# md.net
KiCad netlist of a schematic drawn in EAGLE
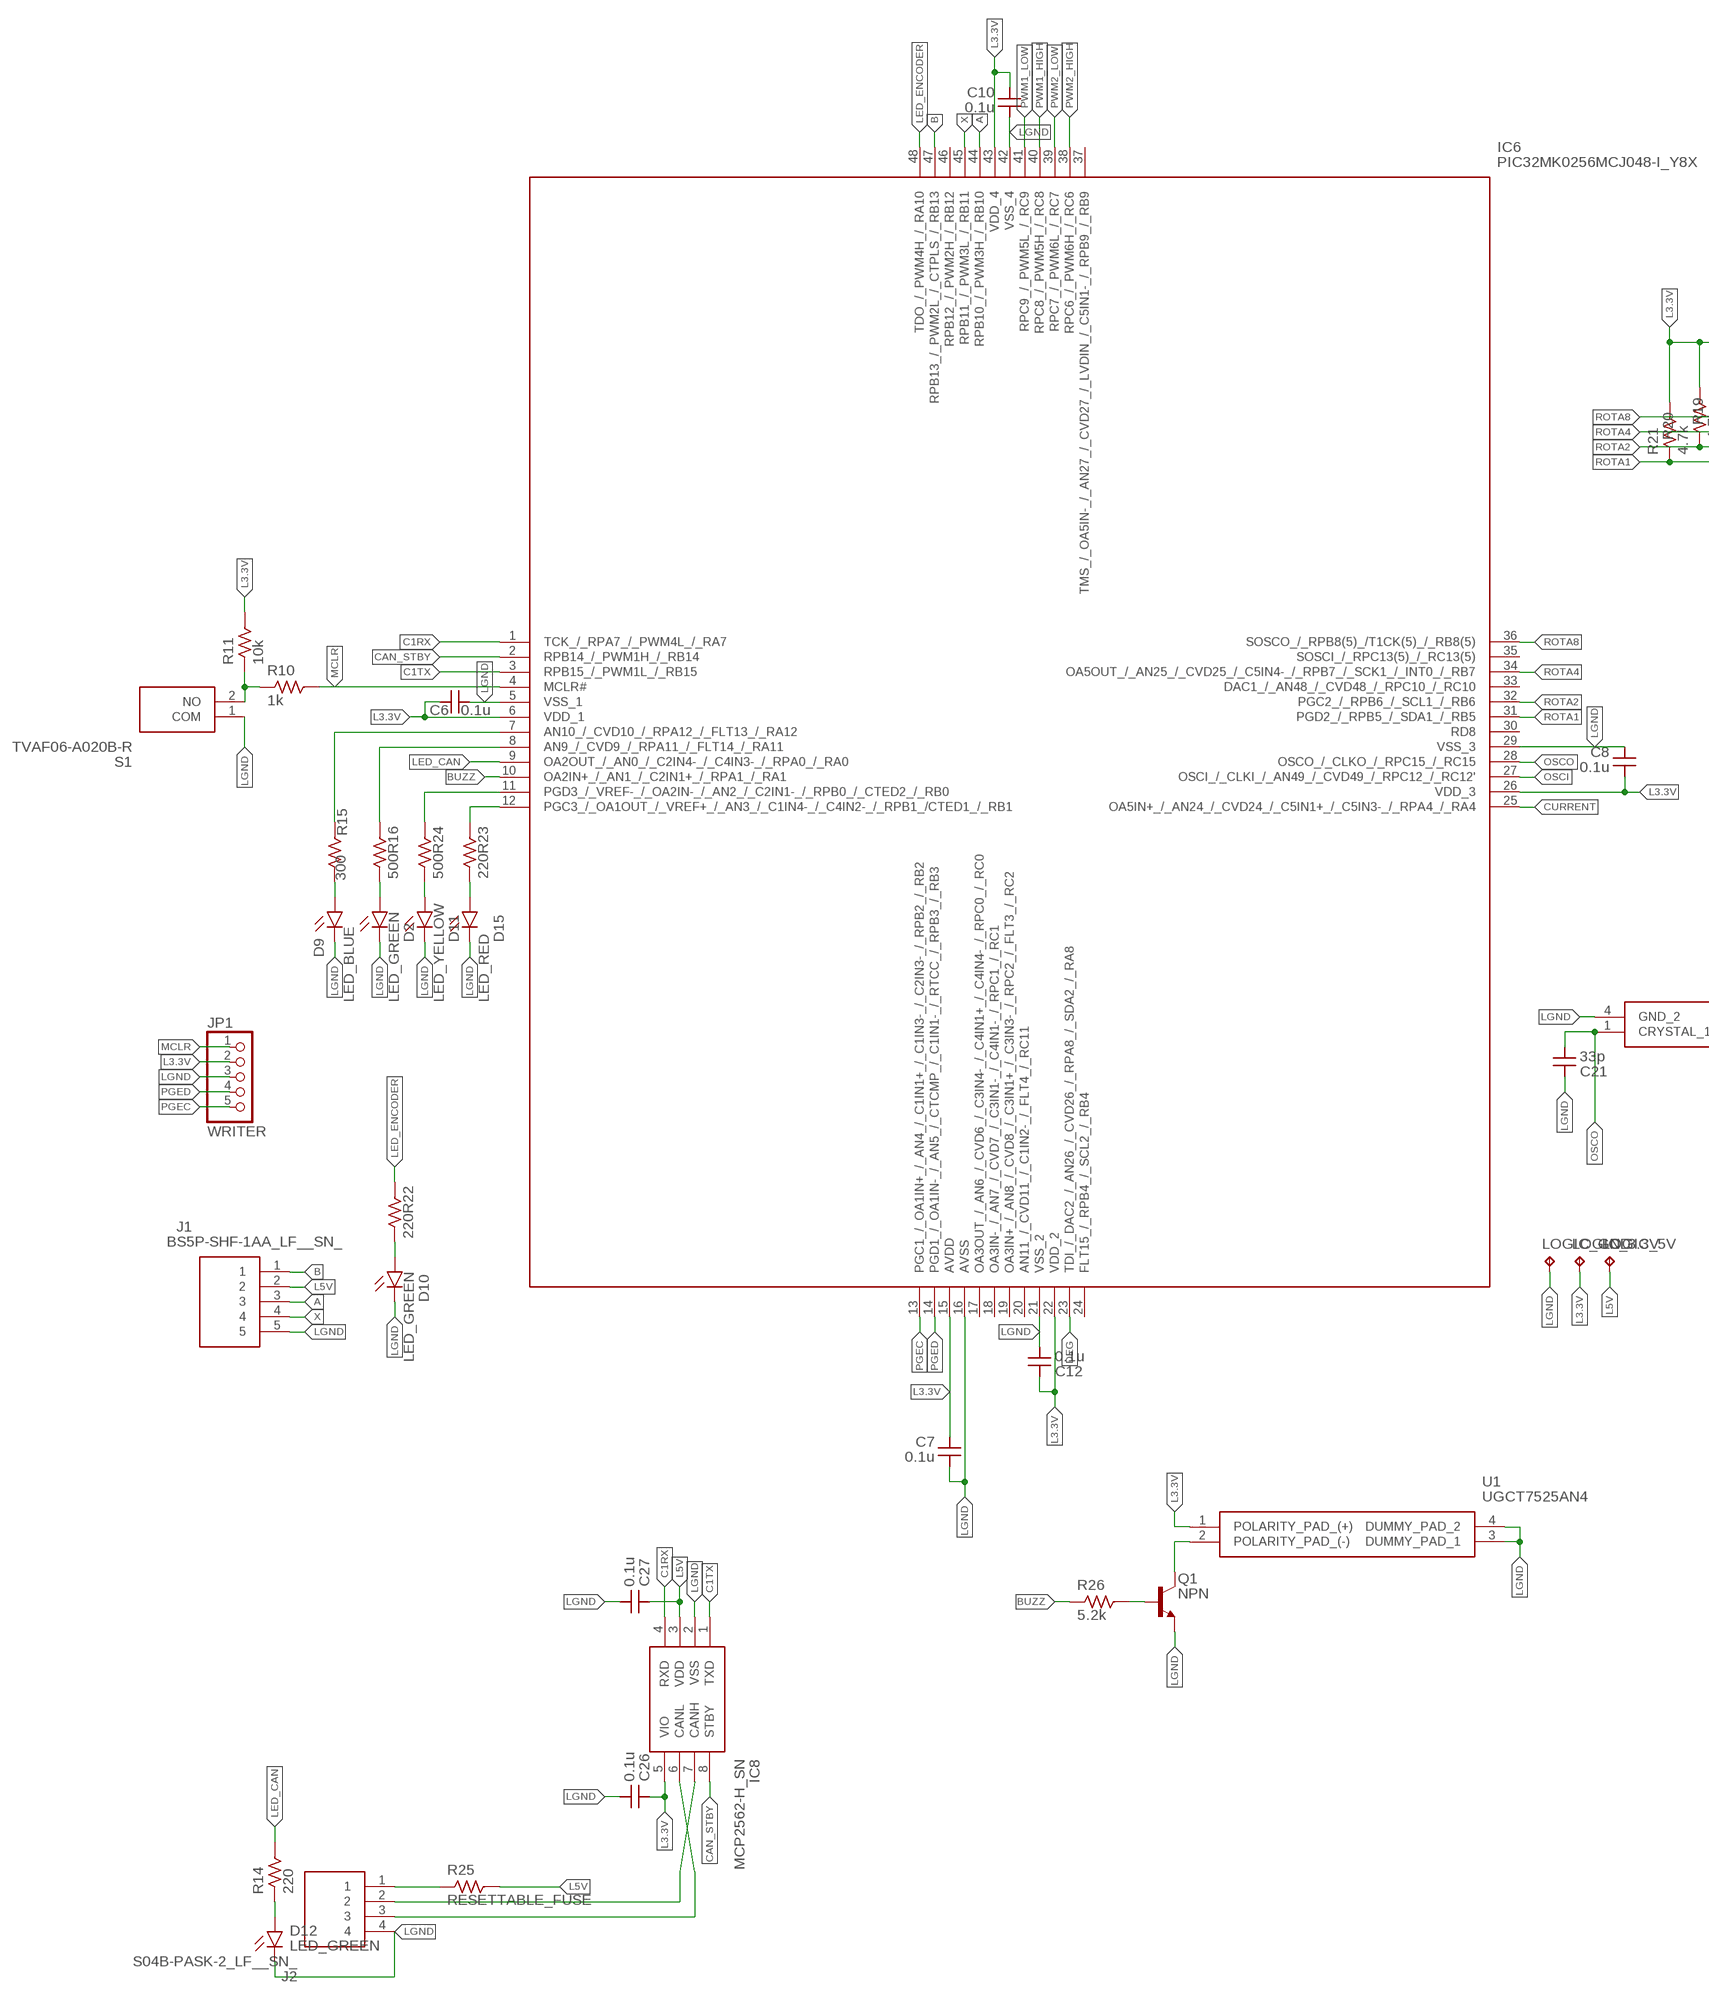
[diagram p0: schematic, sheet 1, part 1 of 2]
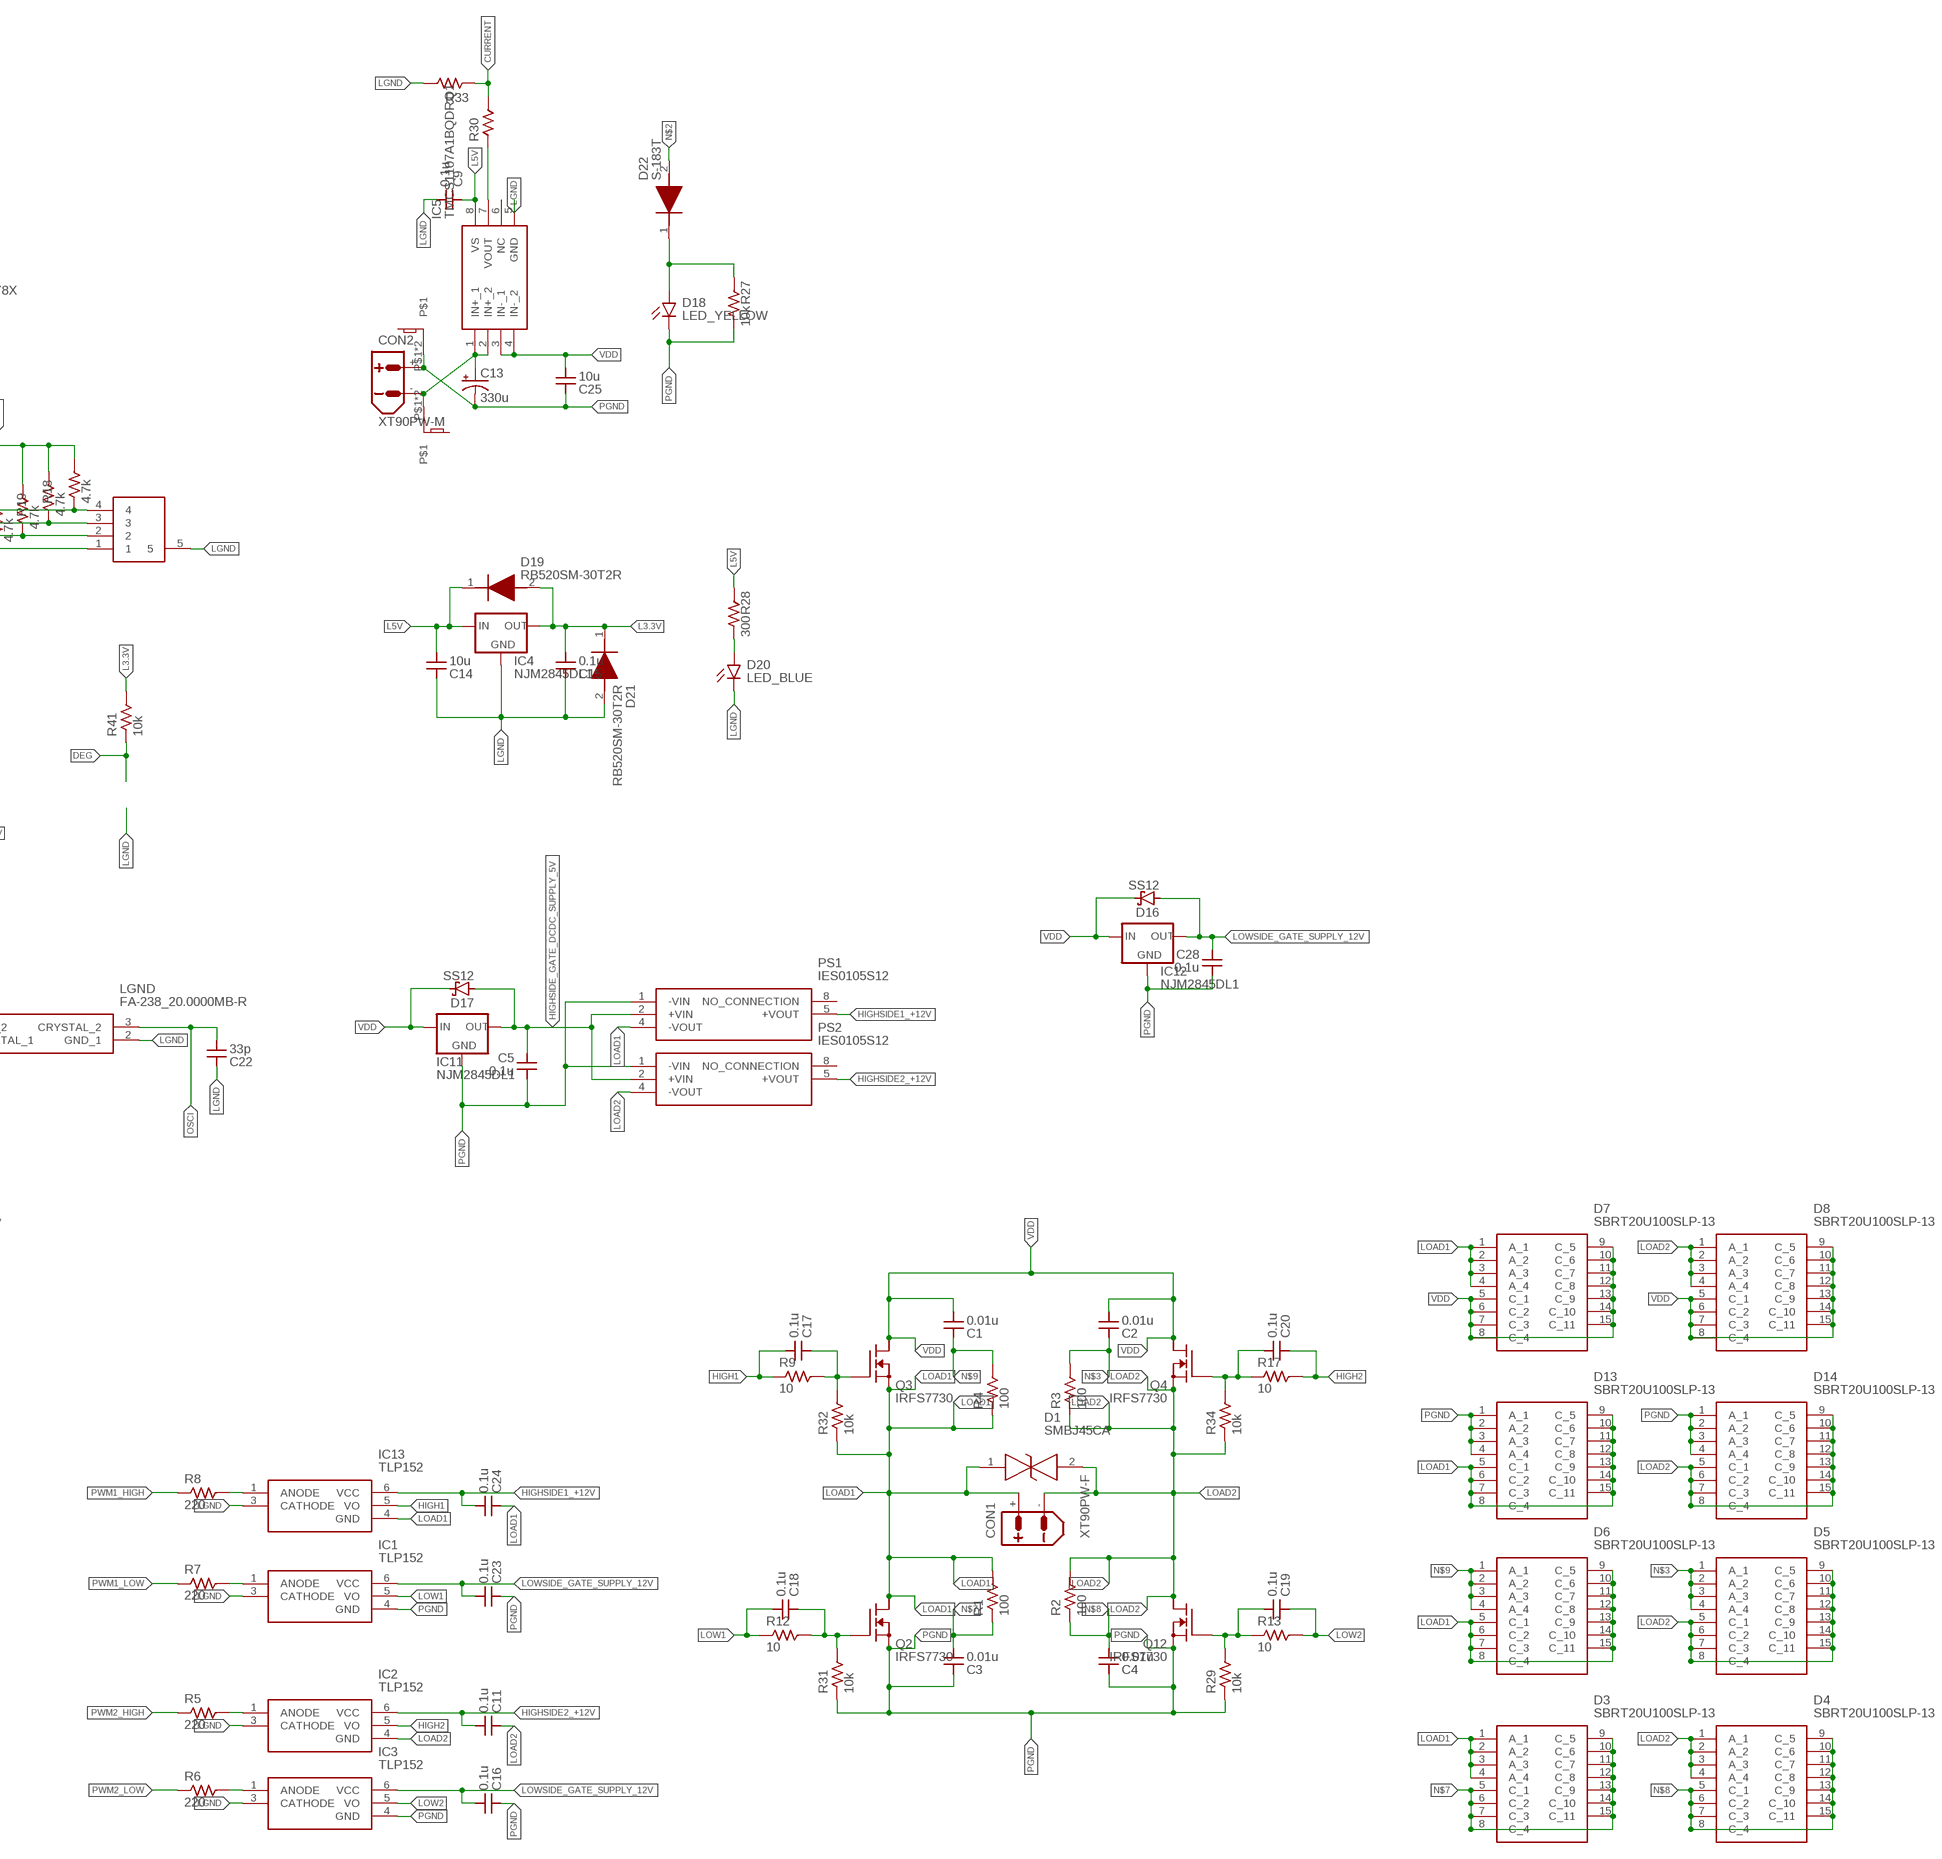
[diagram p1: schematic, sheet 1, part 2 of 2]

(export (version "E")
  (design (tool "Eeschema 10.0.6"))
  (components
    (comp (ref "C1")
      (value "0.01u")
      (footprint "eagle-import:C3216")
      (libsource (lib "eagle-import") (part "CC3216"))
    )
    (comp (ref "C2")
      (value "0.01u")
      (footprint "eagle-import:C3216")
      (libsource (lib "eagle-import") (part "CC3216"))
    )
    (comp (ref "C3")
      (value "0.01u")
      (footprint "eagle-import:C3216")
      (libsource (lib "eagle-import") (part "CC3216"))
    )
    (comp (ref "C4")
      (value "0.01u")
      (footprint "eagle-import:C3216")
      (libsource (lib "eagle-import") (part "CC3216"))
    )
    (comp (ref "C5")
      (value "0.1u")
      (footprint "eagle-import:C1608")
      (libsource (lib "eagle-import") (part "CC1068"))
    )
    (comp (ref "C6")
      (value "0.1u")
      (footprint "eagle-import:C1608")
      (libsource (lib "eagle-import") (part "CC1068"))
    )
    (comp (ref "C7")
      (value "0.1u")
      (footprint "eagle-import:C1608")
      (libsource (lib "eagle-import") (part "CC1068"))
    )
    (comp (ref "C8")
      (value "0.1u")
      (footprint "eagle-import:C1608")
      (libsource (lib "eagle-import") (part "CC1068"))
    )
    (comp (ref "C9")
      (value "0.1u")
      (footprint "eagle-import:C1608")
      (libsource (lib "eagle-import") (part "CC1068"))
    )
    (comp (ref "C10")
      (value "0.1u")
      (footprint "eagle-import:C1608")
      (libsource (lib "eagle-import") (part "CC1068"))
    )
    (comp (ref "C11")
      (value "0.1u")
      (footprint "eagle-import:C1608")
      (libsource (lib "eagle-import") (part "CC1068"))
    )
    (comp (ref "C12")
      (value "0.1u")
      (footprint "eagle-import:C1608")
      (libsource (lib "eagle-import") (part "CC1068"))
    )
    (comp (ref "C13")
      (value "330u")
      (footprint "eagle-import:CAPAE830X1050N")
      (libsource (lib "eagle-import") (part "C-POL-USECAP-8.5MM_"))
    )
    (comp (ref "C14")
      (value "10u")
      (footprint "eagle-import:C1608")
      (libsource (lib "eagle-import") (part "CC1068"))
    )
    (comp (ref "C15")
      (value "0.1u")
      (footprint "eagle-import:C1608")
      (libsource (lib "eagle-import") (part "CC1068"))
    )
    (comp (ref "C16")
      (value "0.1u")
      (footprint "eagle-import:C1608")
      (libsource (lib "eagle-import") (part "CC1068"))
    )
    (comp (ref "C17")
      (value "0.1u")
      (footprint "eagle-import:C1608")
      (libsource (lib "eagle-import") (part "CC1068"))
    )
    (comp (ref "C18")
      (value "0.1u")
      (footprint "eagle-import:C1608")
      (libsource (lib "eagle-import") (part "CC1068"))
    )
    (comp (ref "C19")
      (value "0.1u")
      (footprint "eagle-import:C1608")
      (libsource (lib "eagle-import") (part "CC1068"))
    )
    (comp (ref "C20")
      (value "0.1u")
      (footprint "eagle-import:C1608")
      (libsource (lib "eagle-import") (part "CC1068"))
    )
    (comp (ref "C21")
      (value "33p")
      (footprint "eagle-import:C1608")
      (libsource (lib "eagle-import") (part "CC1068"))
    )
    (comp (ref "C22")
      (value "33p")
      (footprint "eagle-import:C1608")
      (libsource (lib "eagle-import") (part "CC1068"))
    )
    (comp (ref "C23")
      (value "0.1u")
      (footprint "eagle-import:C1608")
      (libsource (lib "eagle-import") (part "CC1068"))
    )
    (comp (ref "C24")
      (value "0.1u")
      (footprint "eagle-import:C1608")
      (libsource (lib "eagle-import") (part "CC1068"))
    )
    (comp (ref "C25")
      (value "10u")
      (footprint "eagle-import:C3216")
      (libsource (lib "eagle-import") (part "CC3216"))
    )
    (comp (ref "C26")
      (value "0.1u")
      (footprint "eagle-import:C1608")
      (libsource (lib "eagle-import") (part "CC1068"))
    )
    (comp (ref "C27")
      (value "0.1u")
      (footprint "eagle-import:C1608")
      (libsource (lib "eagle-import") (part "CC1068"))
    )
    (comp (ref "C28")
      (value "0.1u")
      (footprint "eagle-import:C1608")
      (libsource (lib "eagle-import") (part "CC1068"))
    )
    (comp (ref "CON1")
      (value "XT90PW-F")
      (footprint "eagle-import:XT90PW-F")
      (libsource (lib "eagle-import") (part "XT90PW-F"))
    )
    (comp (ref "CON2")
      (value "XT90PW-M")
      (footprint "eagle-import:XT90PW-M")
      (libsource (lib "eagle-import") (part "XT90PW-M"))
    )
    (comp (ref "D1")
      (value "SMBJ45CA")
      (footprint "eagle-import:DIOM5336X265N")
      (fields (field (name "MOUSER_PART_NUMBER") "576-SMBJ45CA"))
      (libsource (lib "eagle-import") (part "SMBJ45CA"))
    )
    (comp (ref "D2")
      (value "LED_GREEN")
      (footprint "eagle-import:LEDC1608X55N_FLAT-G")
      (libsource (lib "eagle-import") (part "CHIP-FLAT-G_0603-0.55MM"))
    )
    (comp (ref "D3")
      (value "SBRT20U100SLP-13")
      (footprint "eagle-import:SBRT20U100SLP13")
      (fields (field (name "MOUSER_PART_NUMBER") "621-SBRT20U100SLP-13"))
      (libsource (lib "eagle-import") (part "SBRT20U100SLP-13"))
    )
    (comp (ref "D4")
      (value "SBRT20U100SLP-13")
      (footprint "eagle-import:SBRT20U100SLP13")
      (fields (field (name "MOUSER_PART_NUMBER") "621-SBRT20U100SLP-13"))
      (libsource (lib "eagle-import") (part "SBRT20U100SLP-13"))
    )
    (comp (ref "D5")
      (value "SBRT20U100SLP-13")
      (footprint "eagle-import:SBRT20U100SLP13")
      (fields (field (name "MOUSER_PART_NUMBER") "621-SBRT20U100SLP-13"))
      (libsource (lib "eagle-import") (part "SBRT20U100SLP-13"))
    )
    (comp (ref "D6")
      (value "SBRT20U100SLP-13")
      (footprint "eagle-import:SBRT20U100SLP13")
      (fields (field (name "MOUSER_PART_NUMBER") "621-SBRT20U100SLP-13"))
      (libsource (lib "eagle-import") (part "SBRT20U100SLP-13"))
    )
    (comp (ref "D7")
      (value "SBRT20U100SLP-13")
      (footprint "eagle-import:SBRT20U100SLP13")
      (fields (field (name "MOUSER_PART_NUMBER") "621-SBRT20U100SLP-13"))
      (libsource (lib "eagle-import") (part "SBRT20U100SLP-13"))
    )
    (comp (ref "D8")
      (value "SBRT20U100SLP-13")
      (footprint "eagle-import:SBRT20U100SLP13")
      (fields (field (name "MOUSER_PART_NUMBER") "621-SBRT20U100SLP-13"))
      (libsource (lib "eagle-import") (part "SBRT20U100SLP-13"))
    )
    (comp (ref "D9")
      (value "LED_BLUE")
      (footprint "eagle-import:LEDC1608X55N_FLAT-B")
      (libsource (lib "eagle-import") (part "CHIP-FLAT-B_0603-0.55MM"))
    )
    (comp (ref "D10")
      (value "LED_GREEN")
      (footprint "eagle-import:LEDC1608X55N_FLAT-G")
      (libsource (lib "eagle-import") (part "CHIP-FLAT-G_0603-0.55MM"))
    )
    (comp (ref "D11")
      (value "LED_YELLOW")
      (footprint "eagle-import:LEDC1608X55N_FLAT-Y")
      (libsource (lib "eagle-import") (part "CHIP-FLAT-Y_0603-0.55MM"))
    )
    (comp (ref "D12")
      (value "LED_GREEN")
      (footprint "eagle-import:LEDC1608X55N_FLAT-G")
      (libsource (lib "eagle-import") (part "CHIP-FLAT-G_0603-0.55MM"))
    )
    (comp (ref "D13")
      (value "SBRT20U100SLP-13")
      (footprint "eagle-import:SBRT20U100SLP13")
      (fields (field (name "MOUSER_PART_NUMBER") "621-SBRT20U100SLP-13"))
      (libsource (lib "eagle-import") (part "SBRT20U100SLP-13"))
    )
    (comp (ref "D14")
      (value "SBRT20U100SLP-13")
      (footprint "eagle-import:SBRT20U100SLP13")
      (fields (field (name "MOUSER_PART_NUMBER") "621-SBRT20U100SLP-13"))
      (libsource (lib "eagle-import") (part "SBRT20U100SLP-13"))
    )
    (comp (ref "D15")
      (value "LED_RED")
      (footprint "eagle-import:LEDC1608X55N_FLAT-R")
      (libsource (lib "eagle-import") (part "CHIP-FLAT-R_0603-0.55MM"))
    )
    (comp (ref "D16")
      (value "SS12")
      (footprint "eagle-import:SMA")
      (fields
        (field (name "DIGIKEY_PART_NUMBER") "SS12FSCT-ND")
        (field (name "MANUFACTURER") "ON Semiconductor")
        (field (name "CREATED_BY") "PCBLayout.com")
      )
      (libsource (lib "eagle-import") (part "SS12"))
    )
    (comp (ref "D17")
      (value "SS12")
      (footprint "eagle-import:SMA")
      (fields
        (field (name "DIGIKEY_PART_NUMBER") "SS12FSCT-ND")
        (field (name "MANUFACTURER") "ON Semiconductor")
        (field (name "CREATED_BY") "PCBLayout.com")
      )
      (libsource (lib "eagle-import") (part "SS12"))
    )
    (comp (ref "D18")
      (value "LED_YELLOW")
      (footprint "eagle-import:LEDC1608X55N_FLAT-Y")
      (libsource (lib "eagle-import") (part "CHIP-FLAT-Y_0603-0.55MM"))
    )
    (comp (ref "D19")
      (value "RB520SM-30T2R")
      (footprint "eagle-import:DIOC1608X70N")
      (fields (field (name "MOUSER_PART_NUMBER") "755-RB520SM-30T2R"))
      (libsource (lib "eagle-import") (part "RB520SM-30T2R"))
    )
    (comp (ref "D20")
      (value "LED_BLUE")
      (footprint "eagle-import:LEDC1608X55N_FLAT-B")
      (libsource (lib "eagle-import") (part "CHIP-FLAT-B_0603-0.55MM"))
    )
    (comp (ref "D21")
      (value "RB520SM-30T2R")
      (footprint "eagle-import:DIOC1608X70N")
      (fields (field (name "MOUSER_PART_NUMBER") "755-RB520SM-30T2R"))
      (libsource (lib "eagle-import") (part "RB520SM-30T2R"))
    )
    (comp (ref "D22")
      (value "S-183T")
      (footprint "eagle-import:SODFL3516X70N")
      (fields (field (name "MOUSER_PART_NUMBER") "954-S-183T"))
      (libsource (lib "eagle-import") (part "S-183T"))
    )
    (comp (ref "IC1")
      (value "TLP152")
      (footprint "eagle-import:11-4L1S(5-PIN-SOIC)")
      (libsource (lib "eagle-import") (part "TLP152"))
    )
    (comp (ref "IC2")
      (value "TLP152")
      (footprint "eagle-import:11-4L1S(5-PIN-SOIC)")
      (libsource (lib "eagle-import") (part "TLP152"))
    )
    (comp (ref "IC3")
      (value "TLP152")
      (footprint "eagle-import:11-4L1S(5-PIN-SOIC)")
      (libsource (lib "eagle-import") (part "TLP152"))
    )
    (comp (ref "IC4")
      (value "NJM2845DL1")
      (footprint "eagle-import:TO252")
      (libsource (lib "eagle-import") (part "NJM2845DL1"))
    )
    (comp (ref "IC5")
      (value "TMCS1107A1BQDRQ1")
      (footprint "eagle-import:SOIC127P600X175-8N")
      (fields (field (name "MOUSER_PART_NUMBER") "595-TMCS1107A1BQDRQ1"))
      (libsource (lib "eagle-import") (part "TMCS1107A1BQDRQ1"))
    )
    (comp (ref "IC6")
      (value "PIC32MK0256MCJ048-I_Y8X")
      (footprint "eagle-import:QFP50P900X900X120-48N")
      (fields
        (field (name "MANUFACTURER_PART_NUMBER") "PIC32MK0256MCJ048-I/Y8X")
        (field (name "MOUSER_PART_NUMBER") "579-0256MCJ048-I/Y8X")
      )
      (libsource (lib "eagle-import") (part "PIC32MK0256MCJ048-I_Y8X"))
    )
    (comp (ref "IC8")
      (value "MCP2562-H_SN")
      (footprint "eagle-import:SOIC127P600X175-8N")
      (fields
        (field (name "MANUFACTURER_PART_NUMBER") "MCP2562-H/SN")
        (field (name "MOUSER_PART_NUMBER") "579-MCP2562-H/SN")
      )
      (libsource (lib "eagle-import") (part "MCP2562-H_SN"))
    )
    (comp (ref "IC11")
      (value "NJM2845DL1")
      (footprint "eagle-import:TO252")
      (libsource (lib "eagle-import") (part "NJM2845DL1"))
    )
    (comp (ref "IC12")
      (value "NJM2845DL1")
      (footprint "eagle-import:TO252")
      (libsource (lib "eagle-import") (part "NJM2845DL1"))
    )
    (comp (ref "IC13")
      (value "TLP152")
      (footprint "eagle-import:11-4L1S(5-PIN-SOIC)")
      (libsource (lib "eagle-import") (part "TLP152"))
    )
    (comp (ref "J1")
      (value "BS5P-SHF-1AA_LF__SN_")
      (footprint "eagle-import:HDRRA5W64P0X250_1X5_1250X600X5")
      (fields (field (name "MANUFACTURER_PART_NUMBER") "BS5P-SHF-1AA(LF)(SN)"))
      (libsource (lib "eagle-import") (part "BS5P-SHF-1AA_LF__SN_"))
    )
    (comp (ref "J2")
      (value "S04B-PASK-2_LF__SN_")
      (footprint "eagle-import:S04BPASK2LFSN")
      (fields (field (name "ARROW_PART_NUMBER") "S04B-PASK-2(LF)(SN)"))
      (libsource (lib "eagle-import") (part "S04B-PASK-2_LF__SN_"))
    )
    (comp (ref "JP1")
      (value "WRITER")
      (footprint "eagle-import:1X05_90")
      (libsource (lib "eagle-import") (part "PINHD-1X5/90"))
    )
    (comp (ref "LGND")
      (value "FA-238_20.0000MB-R")
      (footprint "eagle-import:FA238200000MBR")
      (fields
        (field (name "MANUFACTURER_PART_NUMBER") "FA-238 20.0000MB-R")
        (field (name "MOUSER_PART_NUMBER") "732-FA-23820B-R")
      )
      (libsource (lib "eagle-import") (part "FA-238_20.0000MB-R"))
    )
    (comp (ref "LOGIC_3.3V")
      (value "TPPAD1-13")
      (footprint "eagle-import:P1-13")
      (libsource (lib "eagle-import") (part "TPPAD1-13"))
    )
    (comp (ref "LOGIC_5V")
      (value "TPPAD1-13")
      (footprint "eagle-import:P1-13")
      (libsource (lib "eagle-import") (part "TPPAD1-13"))
    )
    (comp (ref "LOGIC_GND")
      (value "TPPAD1-13")
      (footprint "eagle-import:P1-13")
      (libsource (lib "eagle-import") (part "TPPAD1-13"))
    )
    (comp (ref "PS1")
      (value "IES0105S12")
      (footprint "eagle-import:IES0105S12")
      (fields (field (name "MOUSER_PART_NUMBER") "209-IES0105S12"))
      (libsource (lib "eagle-import") (part "IES0105S12"))
    )
    (comp (ref "PS2")
      (value "IES0105S12")
      (footprint "eagle-import:IES0105S12")
      (fields (field (name "MOUSER_PART_NUMBER") "209-IES0105S12"))
      (libsource (lib "eagle-import") (part "IES0105S12"))
    )
    (comp (ref "Q1")
      (value "NPN")
      (footprint "eagle-import:SC59")
      (libsource (lib "eagle-import") (part "NPNSC59-BEC_"))
    )
    (comp (ref "Q2")
      (value "IRFS7730")
      (footprint "eagle-import:D2PAK-7")
      (libsource (lib "eagle-import") (part "IRFS7730"))
    )
    (comp (ref "Q3")
      (value "IRFS7730")
      (footprint "eagle-import:D2PAK-7")
      (libsource (lib "eagle-import") (part "IRFS7730"))
    )
    (comp (ref "Q4")
      (value "IRFS7730")
      (footprint "eagle-import:D2PAK-7")
      (libsource (lib "eagle-import") (part "IRFS7730"))
    )
    (comp (ref "Q12")
      (value "IRFS7730")
      (footprint "eagle-import:D2PAK-7")
      (libsource (lib "eagle-import") (part "IRFS7730"))
    )
    (comp (ref "R1")
      (value "100")
      (footprint "eagle-import:C2512")
      (libsource (lib "eagle-import") (part "R2W"))
    )
    (comp (ref "R2")
      (value "100")
      (footprint "eagle-import:C2512")
      (libsource (lib "eagle-import") (part "R2W"))
    )
    (comp (ref "R3")
      (value "100")
      (footprint "eagle-import:C2512")
      (libsource (lib "eagle-import") (part "R2W"))
    )
    (comp (ref "R4")
      (value "100")
      (footprint "eagle-import:C2512")
      (libsource (lib "eagle-import") (part "R2W"))
    )
    (comp (ref "R5")
      (value "220")
      (footprint "eagle-import:C1608")
      (libsource (lib "eagle-import") (part "R1/10W"))
    )
    (comp (ref "R6")
      (value "220")
      (footprint "eagle-import:C1608")
      (libsource (lib "eagle-import") (part "R1/10W"))
    )
    (comp (ref "R7")
      (value "220")
      (footprint "eagle-import:C1608")
      (libsource (lib "eagle-import") (part "R1/10W"))
    )
    (comp (ref "R8")
      (value "220")
      (footprint "eagle-import:C1608")
      (libsource (lib "eagle-import") (part "R1/10W"))
    )
    (comp (ref "R9")
      (value "10")
      (footprint "eagle-import:2010")
      (libsource (lib "eagle-import") (part "R3/4W"))
    )
    (comp (ref "R10")
      (value "1k")
      (footprint "eagle-import:C1608")
      (libsource (lib "eagle-import") (part "R1/10W"))
    )
    (comp (ref "R11")
      (value "10k")
      (footprint "eagle-import:C1608")
      (libsource (lib "eagle-import") (part "R1/10W"))
    )
    (comp (ref "R12")
      (value "10")
      (footprint "eagle-import:2010")
      (libsource (lib "eagle-import") (part "R3/4W"))
    )
    (comp (ref "R13")
      (value "10")
      (footprint "eagle-import:2010")
      (libsource (lib "eagle-import") (part "R3/4W"))
    )
    (comp (ref "R14")
      (value "220")
      (footprint "eagle-import:C1608")
      (libsource (lib "eagle-import") (part "R1/10W"))
    )
    (comp (ref "R15")
      (value "300")
      (footprint "eagle-import:C1608")
      (libsource (lib "eagle-import") (part "R1/10W"))
    )
    (comp (ref "R16")
      (value "500")
      (footprint "eagle-import:C1608")
      (libsource (lib "eagle-import") (part "R1/10W"))
    )
    (comp (ref "R17")
      (value "10")
      (footprint "eagle-import:2010")
      (libsource (lib "eagle-import") (part "R3/4W"))
    )
    (comp (ref "R18")
      (value "4.7k")
      (footprint "eagle-import:C1608")
      (libsource (lib "eagle-import") (part "R1/10W"))
    )
    (comp (ref "R19")
      (value "4.7k")
      (footprint "eagle-import:C1608")
      (libsource (lib "eagle-import") (part "R1/10W"))
    )
    (comp (ref "R20")
      (value "4.7k")
      (footprint "eagle-import:C1608")
      (libsource (lib "eagle-import") (part "R1/10W"))
    )
    (comp (ref "R21")
      (value "4.7k")
      (footprint "eagle-import:C1608")
      (libsource (lib "eagle-import") (part "R1/10W"))
    )
    (comp (ref "R22")
      (value "220")
      (footprint "eagle-import:C1608")
      (libsource (lib "eagle-import") (part "R1/10W"))
    )
    (comp (ref "R23")
      (value "220")
      (footprint "eagle-import:C1608")
      (libsource (lib "eagle-import") (part "R1/10W"))
    )
    (comp (ref "R24")
      (value "500")
      (footprint "eagle-import:C1608")
      (libsource (lib "eagle-import") (part "R1/10W"))
    )
    (comp (ref "R25")
      (value "RESETTABLE_FUSE")
      (footprint "eagle-import:C3216")
      (libsource (lib "eagle-import") (part "R3216(1206)"))
    )
    (comp (ref "R26")
      (value "5.2k")
      (footprint "eagle-import:C1608")
      (libsource (lib "eagle-import") (part "R1/10W"))
    )
    (comp (ref "R27")
      (value "10k")
      (footprint "eagle-import:C1608")
      (libsource (lib "eagle-import") (part "R1/10W"))
    )
    (comp (ref "R28")
      (value "300")
      (footprint "eagle-import:C1608")
      (libsource (lib "eagle-import") (part "R1/10W"))
    )
    (comp (ref "R29")
      (value "10k")
      (footprint "eagle-import:C1608")
      (libsource (lib "eagle-import") (part "R1/10W"))
    )
    (comp (ref "R30")
      (value "R1/10W")
      (footprint "eagle-import:C1608")
      (libsource (lib "eagle-import") (part "R1/10W"))
    )
    (comp (ref "R31")
      (value "10k")
      (footprint "eagle-import:C1608")
      (libsource (lib "eagle-import") (part "R1/10W"))
    )
    (comp (ref "R32")
      (value "10k")
      (footprint "eagle-import:C1608")
      (libsource (lib "eagle-import") (part "R1/10W"))
    )
    (comp (ref "R33")
      (value "R1/10W")
      (footprint "eagle-import:C1608")
      (libsource (lib "eagle-import") (part "R1/10W"))
    )
    (comp (ref "R34")
      (value "10k")
      (footprint "eagle-import:C1608")
      (libsource (lib "eagle-import") (part "R1/10W"))
    )
    (comp (ref "R41")
      (value "10k")
      (footprint "eagle-import:C1608")
      (libsource (lib "eagle-import") (part "R1/10W"))
    )
    (comp (ref "S1")
      (value "TVAF06-A020B-R")
      (footprint "eagle-import:TVAF06A020BR")
      (libsource (lib "eagle-import") (part "TVAF06-A020B-R"))
    )
    (comp (ref "S2")
      (value "DRR4016")
      (footprint "eagle-import:DRR4016")
      (libsource (lib "eagle-import") (part "DRR4016"))
    )
    (comp (ref "SCREW1")
      (value "KIBANNNEZI")
      (footprint "eagle-import:ＰＣＢ－５４Ｌ（Ｍ３）")
      (libsource (lib "eagle-import") (part "KIBANNNEZI"))
    )
    (comp (ref "SCREW2")
      (value "KIBANNNEZI")
      (footprint "eagle-import:ＰＣＢ－５４Ｌ（Ｍ３）")
      (libsource (lib "eagle-import") (part "KIBANNNEZI"))
    )
    (comp (ref "U1")
      (value "UGCT7525AN4")
      (footprint "eagle-import:UGCT7525AN4")
      (libsource (lib "eagle-import") (part "UGCT7525AN4"))
    )
  )
  (nets
    (net (code "1") (name "A") (class "Default")
      (node (ref "IC6") (pin "44") (pinfunction "RPB10_/_PWM3H_/_RB10_44") (pintype "bidirectional"))
      (node (ref "J1") (pin "3") (pinfunction "3_3") (pintype "bidirectional"))
    )
    (net (code "2") (name "B") (class "Default")
      (node (ref "IC6") (pin "47") (pinfunction "RPB13_/_PWM2L_/_CTPLS_/_RB13_47") (pintype "bidirectional"))
      (node (ref "J1") (pin "1") (pinfunction "1_1") (pintype "bidirectional"))
    )
    (net (code "3") (name "BUZZ") (class "Default")
      (node (ref "IC6") (pin "10") (pinfunction "OA2IN+_/_AN1_/_C2IN1+_/_RPA1_/_RA1_10") (pintype "bidirectional"))
      (node (ref "R26") (pin "1") (pinfunction "P$1_1") (pintype "passive"))
    )
    (net (code "4") (name "C1RX") (class "Default")
      (node (ref "IC6") (pin "1") (pinfunction "TCK_/_RPA7_/_PWM4L_/_RA7_1") (pintype "bidirectional"))
      (node (ref "IC8") (pin "4") (pinfunction "RXD_4") (pintype "bidirectional"))
    )
    (net (code "5") (name "C1TX") (class "Default")
      (node (ref "IC6") (pin "3") (pinfunction "RPB15_/_PWM1L_/_RB15_3") (pintype "bidirectional"))
      (node (ref "IC8") (pin "1") (pinfunction "TXD_1") (pintype "bidirectional"))
    )
    (net (code "6") (name "CAN_STBY") (class "Default")
      (node (ref "IC6") (pin "2") (pinfunction "RPB14_/_PWM1H_/_RB14_2") (pintype "bidirectional"))
      (node (ref "IC8") (pin "8") (pinfunction "STBY_8") (pintype "bidirectional"))
    )
    (net (code "7") (name "CURRENT") (class "Default")
      (node (ref "IC6") (pin "25") (pinfunction "OA5IN+_/_AN24_/_CVD24_/_C5IN1+_/_C5IN3-_/_RPA4_/_RA4_25") (pintype "bidirectional"))
      (node (ref "R30") (pin "2") (pinfunction "P$2_2") (pintype "passive"))
      (node (ref "R33") (pin "1") (pinfunction "P$1_1") (pintype "passive"))
    )
    (net (code "8") (name "DEG") (class "Default")
      (node (ref "IC6") (pin "23") (pinfunction "TDI_/_DAC2_/_AN26_/_CVD26_/_RPA8_/_SDA2_/_RA8_23") (pintype "bidirectional"))
      (node (ref "R41") (pin "1") (pinfunction "P$1_1") (pintype "passive"))
    )
    (net (code "9") (name "HIGH1") (class "Default")
      (node (ref "C17") (pin "1") (pinfunction "P$1_1") (pintype "passive"))
      (node (ref "IC13") (pin "5") (pinfunction "VO_5") (pintype "bidirectional"))
      (node (ref "R9") (pin "P$1") (pinfunction "P$1_P$1") (pintype "passive"))
    )
    (net (code "10") (name "HIGH2") (class "Default")
      (node (ref "C20") (pin "2") (pinfunction "P$2_2") (pintype "passive"))
      (node (ref "IC2") (pin "5") (pinfunction "VO_5") (pintype "bidirectional"))
      (node (ref "R17") (pin "P$2") (pinfunction "P$2_P$2") (pintype "passive"))
    )
    (net (code "11") (name "HIGHSIDE1_+12V") (class "Default")
      (node (ref "C24") (pin "1") (pinfunction "P$1_1") (pintype "passive"))
      (node (ref "IC13") (pin "6") (pinfunction "VCC_6") (pintype "bidirectional"))
      (node (ref "PS1") (pin "5") (pinfunction "+VOUT_5") (pintype "bidirectional"))
    )
    (net (code "12") (name "HIGHSIDE2_+12V") (class "Default")
      (node (ref "C11") (pin "1") (pinfunction "P$1_1") (pintype "passive"))
      (node (ref "IC2") (pin "6") (pinfunction "VCC_6") (pintype "bidirectional"))
      (node (ref "PS2") (pin "5") (pinfunction "+VOUT_5") (pintype "bidirectional"))
    )
    (net (code "13") (name "HIGHSIDE_GATE_DCDC_SUPPLY_5V") (class "Default")
      (node (ref "C5") (pin "2") (pinfunction "P$2_2") (pintype "passive"))
      (node (ref "D17") (pin "A") (pinfunction "A_A") (pintype "passive"))
      (node (ref "IC11") (pin "3") (pinfunction "OUT_3") (pintype "passive"))
      (node (ref "PS1") (pin "2") (pinfunction "+VIN_2") (pintype "bidirectional"))
      (node (ref "PS2") (pin "2") (pinfunction "+VIN_2") (pintype "bidirectional"))
    )
    (net (code "14") (name "L3.3V") (class "Default")
      (node (ref "C10") (pin "2") (pinfunction "P$2_2") (pintype "passive"))
      (node (ref "C12") (pin "2") (pinfunction "P$2_2") (pintype "passive"))
      (node (ref "C15") (pin "1") (pinfunction "P$1_1") (pintype "passive"))
      (node (ref "C26") (pin "2") (pinfunction "P$2_2") (pintype "passive"))
      (node (ref "C6") (pin "2") (pinfunction "P$2_2") (pintype "passive"))
      (node (ref "C7") (pin "2") (pinfunction "P$2_2") (pintype "passive"))
      (node (ref "C8") (pin "1") (pinfunction "P$1_1") (pintype "passive"))
      (node (ref "D19") (pin "2") (pinfunction "A_2") (pintype "bidirectional"))
      (node (ref "D21") (pin "1") (pinfunction "K_1") (pintype "bidirectional"))
      (node (ref "IC4") (pin "3") (pinfunction "OUT_3") (pintype "passive"))
      (node (ref "IC6") (pin "15") (pinfunction "AVDD_15") (pintype "bidirectional"))
      (node (ref "IC6") (pin "22") (pinfunction "VDD_2_22") (pintype "bidirectional"))
      (node (ref "IC6") (pin "26") (pinfunction "VDD_3_26") (pintype "bidirectional"))
      (node (ref "IC6") (pin "43") (pinfunction "VDD_4_43") (pintype "bidirectional"))
      (node (ref "IC6") (pin "6") (pinfunction "VDD_1_6") (pintype "bidirectional"))
      (node (ref "IC8") (pin "5") (pinfunction "VIO_5") (pintype "bidirectional"))
      (node (ref "JP1") (pin "2") (pinfunction "2_2") (pintype "passive"))
      (node (ref "LOGIC_3.3V") (pin "TP") (pinfunction "TP_TP") (pintype "input"))
      (node (ref "R11") (pin "2") (pinfunction "P$2_2") (pintype "passive"))
      (node (ref "R18") (pin "2") (pinfunction "P$2_2") (pintype "passive"))
      (node (ref "R19") (pin "2") (pinfunction "P$2_2") (pintype "passive"))
      (node (ref "R20") (pin "2") (pinfunction "P$2_2") (pintype "passive"))
      (node (ref "R21") (pin "2") (pinfunction "P$2_2") (pintype "passive"))
      (node (ref "R41") (pin "2") (pinfunction "P$2_2") (pintype "passive"))
      (node (ref "U1") (pin "1") (pinfunction "POLARITY_PAD_(+)_1") (pintype "bidirectional"))
    )
    (net (code "15") (name "L5V") (class "Default")
      (node (ref "C14") (pin "1") (pinfunction "P$1_1") (pintype "passive"))
      (node (ref "C27") (pin "2") (pinfunction "P$2_2") (pintype "passive"))
      (node (ref "C9") (pin "2") (pinfunction "P$2_2") (pintype "passive"))
      (node (ref "D19") (pin "1") (pinfunction "K_1") (pintype "bidirectional"))
      (node (ref "IC4") (pin "1") (pinfunction "IN_1") (pintype "input"))
      (node (ref "IC5") (pin "8") (pinfunction "VS_8") (pintype "bidirectional"))
      (node (ref "IC8") (pin "3") (pinfunction "VDD_3") (pintype "bidirectional"))
      (node (ref "J1") (pin "2") (pinfunction "2_2") (pintype "bidirectional"))
      (node (ref "LOGIC_5V") (pin "TP") (pinfunction "TP_TP") (pintype "input"))
      (node (ref "R25") (pin "2") (pinfunction "P$2_2") (pintype "passive"))
      (node (ref "R28") (pin "2") (pinfunction "P$2_2") (pintype "passive"))
    )
    (net (code "16") (name "LED_CAN") (class "Default")
      (node (ref "IC6") (pin "9") (pinfunction "OA2OUT_/_AN0_/_C2IN4-_/_C4IN3-_/_RPA0_/_RA0_9") (pintype "bidirectional"))
      (node (ref "R14") (pin "2") (pinfunction "P$2_2") (pintype "passive"))
    )
    (net (code "17") (name "LED_ENCODER") (class "Default")
      (node (ref "IC6") (pin "48") (pinfunction "TDO_/_PWM4H_/_RA10_48") (pintype "bidirectional"))
      (node (ref "R22") (pin "2") (pinfunction "P$2_2") (pintype "passive"))
    )
    (net (code "18") (name "LGND") (class "Default")
      (node (ref "C10") (pin "1") (pinfunction "P$1_1") (pintype "passive"))
      (node (ref "C12") (pin "1") (pinfunction "P$1_1") (pintype "passive"))
      (node (ref "C14") (pin "2") (pinfunction "P$2_2") (pintype "passive"))
      (node (ref "C15") (pin "2") (pinfunction "P$2_2") (pintype "passive"))
      (node (ref "C21") (pin "2") (pinfunction "P$2_2") (pintype "passive"))
      (node (ref "C22") (pin "2") (pinfunction "P$2_2") (pintype "passive"))
      (node (ref "C26") (pin "1") (pinfunction "P$1_1") (pintype "passive"))
      (node (ref "C27") (pin "1") (pinfunction "P$1_1") (pintype "passive"))
      (node (ref "C6") (pin "1") (pinfunction "P$1_1") (pintype "passive"))
      (node (ref "C7") (pin "1") (pinfunction "P$1_1") (pintype "passive"))
      (node (ref "C8") (pin "2") (pinfunction "P$2_2") (pintype "passive"))
      (node (ref "C9") (pin "1") (pinfunction "P$1_1") (pintype "passive"))
      (node (ref "D10") (pin "C") (pinfunction "C_C") (pintype "passive"))
      (node (ref "D11") (pin "C") (pinfunction "C_C") (pintype "passive"))
      (node (ref "D12") (pin "C") (pinfunction "C_C") (pintype "passive"))
      (node (ref "D15") (pin "C") (pinfunction "C_C") (pintype "passive"))
      (node (ref "D2") (pin "C") (pinfunction "C_C") (pintype "passive"))
      (node (ref "D20") (pin "C") (pinfunction "C_C") (pintype "passive"))
      (node (ref "D21") (pin "2") (pinfunction "A_2") (pintype "bidirectional"))
      (node (ref "D9") (pin "C") (pinfunction "C_C") (pintype "passive"))
      (node (ref "IC1") (pin "3") (pinfunction "CATHODE_3") (pintype "bidirectional"))
      (node (ref "IC13") (pin "3") (pinfunction "CATHODE_3") (pintype "bidirectional"))
      (node (ref "IC2") (pin "3") (pinfunction "CATHODE_3") (pintype "bidirectional"))
      (node (ref "IC3") (pin "3") (pinfunction "CATHODE_3") (pintype "bidirectional"))
      (node (ref "IC4") (pin "2") (pinfunction "GND_2") (pintype "input"))
      (node (ref "IC5") (pin "5") (pinfunction "GND_5") (pintype "bidirectional"))
      (node (ref "IC6") (pin "16") (pinfunction "AVSS_16") (pintype "bidirectional"))
      (node (ref "IC6") (pin "21") (pinfunction "VSS_2_21") (pintype "bidirectional"))
      (node (ref "IC6") (pin "29") (pinfunction "VSS_3_29") (pintype "bidirectional"))
      (node (ref "IC6") (pin "42") (pinfunction "VSS_4_42") (pintype "bidirectional"))
      (node (ref "IC6") (pin "5") (pinfunction "VSS_1_5") (pintype "bidirectional"))
      (node (ref "IC8") (pin "2") (pinfunction "VSS_2") (pintype "bidirectional"))
      (node (ref "J1") (pin "5") (pinfunction "5_5") (pintype "bidirectional"))
      (node (ref "J2") (pin "4") (pinfunction "4_4") (pintype "bidirectional"))
      (node (ref "JP1") (pin "3") (pinfunction "3_3") (pintype "passive"))
      (node (ref "LGND") (pin "2") (pinfunction "GND_1_2") (pintype "bidirectional"))
      (node (ref "LGND") (pin "4") (pinfunction "GND_2_4") (pintype "bidirectional"))
      (node (ref "LOGIC_GND") (pin "TP") (pinfunction "TP_TP") (pintype "input"))
      (node (ref "Q1") (pin "E") (pinfunction "E_E") (pintype "passive"))
      (node (ref "R33") (pin "2") (pinfunction "P$2_2") (pintype "passive"))
      (node (ref "S1") (pin "1") (pinfunction "COM_1") (pintype "bidirectional"))
      (node (ref "S2") (pin "5") (pinfunction "5_5") (pintype "bidirectional"))
      (node (ref "U1") (pin "3") (pinfunction "DUMMY_PAD_1_3") (pintype "bidirectional"))
      (node (ref "U1") (pin "4") (pinfunction "DUMMY_PAD_2_4") (pintype "bidirectional"))
    )
    (net (code "19") (name "LOAD1") (class "Default")
      (node (ref "C24") (pin "2") (pinfunction "P$2_2") (pintype "passive"))
      (node (ref "CON1") (pin "+") (pinfunction "+_+") (pintype "power_in"))
      (node (ref "D1") (pin "1") (pinfunction "1_1") (pintype "bidirectional"))
      (node (ref "D13") (pin "10") (pinfunction "C_6_10") (pintype "bidirectional"))
      (node (ref "D13") (pin "11") (pinfunction "C_7_11") (pintype "bidirectional"))
      (node (ref "D13") (pin "12") (pinfunction "C_8_12") (pintype "bidirectional"))
      (node (ref "D13") (pin "13") (pinfunction "C_9_13") (pintype "bidirectional"))
      (node (ref "D13") (pin "14") (pinfunction "C_10_14") (pintype "bidirectional"))
      (node (ref "D13") (pin "15") (pinfunction "C_11_15") (pintype "bidirectional"))
      (node (ref "D13") (pin "5") (pinfunction "C_1_5") (pintype "bidirectional"))
      (node (ref "D13") (pin "6") (pinfunction "C_2_6") (pintype "bidirectional"))
      (node (ref "D13") (pin "7") (pinfunction "C_3_7") (pintype "bidirectional"))
      (node (ref "D13") (pin "8") (pinfunction "C_4_8") (pintype "bidirectional"))
      (node (ref "D13") (pin "9") (pinfunction "C_5_9") (pintype "bidirectional"))
      (node (ref "D3") (pin "1") (pinfunction "A_1_1") (pintype "bidirectional"))
      (node (ref "D3") (pin "2") (pinfunction "A_2_2") (pintype "bidirectional"))
      (node (ref "D3") (pin "3") (pinfunction "A_3_3") (pintype "bidirectional"))
      (node (ref "D3") (pin "4") (pinfunction "A_4_4") (pintype "bidirectional"))
      (node (ref "D6") (pin "10") (pinfunction "C_6_10") (pintype "bidirectional"))
      (node (ref "D6") (pin "11") (pinfunction "C_7_11") (pintype "bidirectional"))
      (node (ref "D6") (pin "12") (pinfunction "C_8_12") (pintype "bidirectional"))
      (node (ref "D6") (pin "13") (pinfunction "C_9_13") (pintype "bidirectional"))
      (node (ref "D6") (pin "14") (pinfunction "C_10_14") (pintype "bidirectional"))
      (node (ref "D6") (pin "15") (pinfunction "C_11_15") (pintype "bidirectional"))
      (node (ref "D6") (pin "5") (pinfunction "C_1_5") (pintype "bidirectional"))
      (node (ref "D6") (pin "6") (pinfunction "C_2_6") (pintype "bidirectional"))
      (node (ref "D6") (pin "7") (pinfunction "C_3_7") (pintype "bidirectional"))
      (node (ref "D6") (pin "8") (pinfunction "C_4_8") (pintype "bidirectional"))
      (node (ref "D6") (pin "9") (pinfunction "C_5_9") (pintype "bidirectional"))
      (node (ref "D7") (pin "1") (pinfunction "A_1_1") (pintype "bidirectional"))
      (node (ref "D7") (pin "2") (pinfunction "A_2_2") (pintype "bidirectional"))
      (node (ref "D7") (pin "3") (pinfunction "A_3_3") (pintype "bidirectional"))
      (node (ref "D7") (pin "4") (pinfunction "A_4_4") (pintype "bidirectional"))
      (node (ref "IC13") (pin "4") (pinfunction "GND_4") (pintype "bidirectional"))
      (node (ref "PS1") (pin "4") (pinfunction "-VOUT_4") (pintype "bidirectional"))
      (node (ref "Q2") (pin "D") (pinfunction "NｃｈD_D") (pintype "passive"))
      (node (ref "Q3") (pin "S1") (pinfunction "NｃｈS_S1") (pintype "passive"))
      (node (ref "Q3") (pin "S2") (pinfunction "NｃｈS_S2") (pintype "passive"))
      (node (ref "Q3") (pin "S3") (pinfunction "NｃｈS_S3") (pintype "passive"))
      (node (ref "Q3") (pin "S4") (pinfunction "NｃｈS_S4") (pintype "passive"))
      (node (ref "Q3") (pin "S5") (pinfunction "NｃｈS_S5") (pintype "passive"))
      (node (ref "R1") (pin "2") (pinfunction "P$2_2") (pintype "passive"))
      (node (ref "R32") (pin "1") (pinfunction "P$1_1") (pintype "passive"))
      (node (ref "R4") (pin "1") (pinfunction "P$1_1") (pintype "passive"))
    )
    (net (code "20") (name "LOAD2") (class "Default")
      (node (ref "C11") (pin "2") (pinfunction "P$2_2") (pintype "passive"))
      (node (ref "CON1") (pin "-") (pinfunction "-_-") (pintype "power_in"))
      (node (ref "D1") (pin "2") (pinfunction "2_2") (pintype "bidirectional"))
      (node (ref "D14") (pin "10") (pinfunction "C_6_10") (pintype "bidirectional"))
      (node (ref "D14") (pin "11") (pinfunction "C_7_11") (pintype "bidirectional"))
      (node (ref "D14") (pin "12") (pinfunction "C_8_12") (pintype "bidirectional"))
      (node (ref "D14") (pin "13") (pinfunction "C_9_13") (pintype "bidirectional"))
      (node (ref "D14") (pin "14") (pinfunction "C_10_14") (pintype "bidirectional"))
      (node (ref "D14") (pin "15") (pinfunction "C_11_15") (pintype "bidirectional"))
      (node (ref "D14") (pin "5") (pinfunction "C_1_5") (pintype "bidirectional"))
      (node (ref "D14") (pin "6") (pinfunction "C_2_6") (pintype "bidirectional"))
      (node (ref "D14") (pin "7") (pinfunction "C_3_7") (pintype "bidirectional"))
      (node (ref "D14") (pin "8") (pinfunction "C_4_8") (pintype "bidirectional"))
      (node (ref "D14") (pin "9") (pinfunction "C_5_9") (pintype "bidirectional"))
      (node (ref "D4") (pin "1") (pinfunction "A_1_1") (pintype "bidirectional"))
      (node (ref "D4") (pin "2") (pinfunction "A_2_2") (pintype "bidirectional"))
      (node (ref "D4") (pin "3") (pinfunction "A_3_3") (pintype "bidirectional"))
      (node (ref "D4") (pin "4") (pinfunction "A_4_4") (pintype "bidirectional"))
      (node (ref "D5") (pin "10") (pinfunction "C_6_10") (pintype "bidirectional"))
      (node (ref "D5") (pin "11") (pinfunction "C_7_11") (pintype "bidirectional"))
      (node (ref "D5") (pin "12") (pinfunction "C_8_12") (pintype "bidirectional"))
      (node (ref "D5") (pin "13") (pinfunction "C_9_13") (pintype "bidirectional"))
      (node (ref "D5") (pin "14") (pinfunction "C_10_14") (pintype "bidirectional"))
      (node (ref "D5") (pin "15") (pinfunction "C_11_15") (pintype "bidirectional"))
      (node (ref "D5") (pin "5") (pinfunction "C_1_5") (pintype "bidirectional"))
      (node (ref "D5") (pin "6") (pinfunction "C_2_6") (pintype "bidirectional"))
      (node (ref "D5") (pin "7") (pinfunction "C_3_7") (pintype "bidirectional"))
      (node (ref "D5") (pin "8") (pinfunction "C_4_8") (pintype "bidirectional"))
      (node (ref "D5") (pin "9") (pinfunction "C_5_9") (pintype "bidirectional"))
      (node (ref "D8") (pin "1") (pinfunction "A_1_1") (pintype "bidirectional"))
      (node (ref "D8") (pin "2") (pinfunction "A_2_2") (pintype "bidirectional"))
      (node (ref "D8") (pin "3") (pinfunction "A_3_3") (pintype "bidirectional"))
      (node (ref "D8") (pin "4") (pinfunction "A_4_4") (pintype "bidirectional"))
      (node (ref "IC2") (pin "4") (pinfunction "GND_4") (pintype "bidirectional"))
      (node (ref "PS2") (pin "4") (pinfunction "-VOUT_4") (pintype "bidirectional"))
      (node (ref "Q12") (pin "D") (pinfunction "NｃｈD_D") (pintype "passive"))
      (node (ref "Q4") (pin "S1") (pinfunction "NｃｈS_S1") (pintype "passive"))
      (node (ref "Q4") (pin "S2") (pinfunction "NｃｈS_S2") (pintype "passive"))
      (node (ref "Q4") (pin "S3") (pinfunction "NｃｈS_S3") (pintype "passive"))
      (node (ref "Q4") (pin "S4") (pinfunction "NｃｈS_S4") (pintype "passive"))
      (node (ref "Q4") (pin "S5") (pinfunction "NｃｈS_S5") (pintype "passive"))
      (node (ref "R2") (pin "2") (pinfunction "P$2_2") (pintype "passive"))
      (node (ref "R3") (pin "1") (pinfunction "P$1_1") (pintype "passive"))
      (node (ref "R34") (pin "1") (pinfunction "P$1_1") (pintype "passive"))
    )
    (net (code "21") (name "LOW1") (class "Default")
      (node (ref "C18") (pin "1") (pinfunction "P$1_1") (pintype "passive"))
      (node (ref "IC1") (pin "5") (pinfunction "VO_5") (pintype "bidirectional"))
      (node (ref "R12") (pin "P$1") (pinfunction "P$1_P$1") (pintype "passive"))
    )
    (net (code "22") (name "LOW2") (class "Default")
      (node (ref "C19") (pin "2") (pinfunction "P$2_2") (pintype "passive"))
      (node (ref "IC3") (pin "5") (pinfunction "VO_5") (pintype "bidirectional"))
      (node (ref "R13") (pin "P$2") (pinfunction "P$2_P$2") (pintype "passive"))
    )
    (net (code "23") (name "LOWSIDE_GATE_SUPPLY_12V") (class "Default")
      (node (ref "C16") (pin "1") (pinfunction "P$1_1") (pintype "passive"))
      (node (ref "C23") (pin "1") (pinfunction "P$1_1") (pintype "passive"))
      (node (ref "C28") (pin "2") (pinfunction "P$2_2") (pintype "passive"))
      (node (ref "D16") (pin "A") (pinfunction "A_A") (pintype "passive"))
      (node (ref "IC1") (pin "6") (pinfunction "VCC_6") (pintype "bidirectional"))
      (node (ref "IC12") (pin "3") (pinfunction "OUT_3") (pintype "passive"))
      (node (ref "IC3") (pin "6") (pinfunction "VCC_6") (pintype "bidirectional"))
    )
    (net (code "24") (name "MCLR") (class "Default")
      (node (ref "IC6") (pin "4") (pinfunction "MCLR#_4") (pintype "bidirectional"))
      (node (ref "JP1") (pin "1") (pinfunction "1_1") (pintype "passive"))
      (node (ref "R10") (pin "2") (pinfunction "P$2_2") (pintype "passive"))
    )
    (net (code "25") (name "N$2") (class "Default")
      (node (ref "C13") (pin "1") (pinfunction "+_1") (pintype "passive"))
      (node (ref "CON2") (pin "-") (pinfunction "-_-") (pintype "power_in"))
      (node (ref "D22") (pin "2") (pinfunction "A_2") (pintype "bidirectional"))
      (node (ref "IC5") (pin "1") (pinfunction "IN+_1_1") (pintype "bidirectional"))
      (node (ref "IC5") (pin "2") (pinfunction "IN+_2_2") (pintype "bidirectional"))
      (node (ref "SCREW1") (pin "P$1") (pinfunction "P$1_P$1") (pintype "bidirectional"))
      (node (ref "SCREW1") (pin "P$2") (pinfunction "P$1_P$2") (pintype "bidirectional"))
    )
    (net (code "26") (name "N$3") (class "Default")
      (node (ref "C2") (pin "2") (pinfunction "P$2_2") (pintype "passive"))
      (node (ref "D5") (pin "1") (pinfunction "A_1_1") (pintype "bidirectional"))
      (node (ref "D5") (pin "2") (pinfunction "A_2_2") (pintype "bidirectional"))
      (node (ref "D5") (pin "3") (pinfunction "A_3_3") (pintype "bidirectional"))
      (node (ref "D5") (pin "4") (pinfunction "A_4_4") (pintype "bidirectional"))
      (node (ref "R3") (pin "2") (pinfunction "P$2_2") (pintype "passive"))
    )
    (net (code "27") (name "N$7") (class "Default")
      (node (ref "C3") (pin "1") (pinfunction "P$1_1") (pintype "passive"))
      (node (ref "D3") (pin "10") (pinfunction "C_6_10") (pintype "bidirectional"))
      (node (ref "D3") (pin "11") (pinfunction "C_7_11") (pintype "bidirectional"))
      (node (ref "D3") (pin "12") (pinfunction "C_8_12") (pintype "bidirectional"))
      (node (ref "D3") (pin "13") (pinfunction "C_9_13") (pintype "bidirectional"))
      (node (ref "D3") (pin "14") (pinfunction "C_10_14") (pintype "bidirectional"))
      (node (ref "D3") (pin "15") (pinfunction "C_11_15") (pintype "bidirectional"))
      (node (ref "D3") (pin "5") (pinfunction "C_1_5") (pintype "bidirectional"))
      (node (ref "D3") (pin "6") (pinfunction "C_2_6") (pintype "bidirectional"))
      (node (ref "D3") (pin "7") (pinfunction "C_3_7") (pintype "bidirectional"))
      (node (ref "D3") (pin "8") (pinfunction "C_4_8") (pintype "bidirectional"))
      (node (ref "D3") (pin "9") (pinfunction "C_5_9") (pintype "bidirectional"))
      (node (ref "R1") (pin "1") (pinfunction "P$1_1") (pintype "passive"))
    )
    (net (code "28") (name "N$8") (class "Default")
      (node (ref "C4") (pin "1") (pinfunction "P$1_1") (pintype "passive"))
      (node (ref "D4") (pin "10") (pinfunction "C_6_10") (pintype "bidirectional"))
      (node (ref "D4") (pin "11") (pinfunction "C_7_11") (pintype "bidirectional"))
      (node (ref "D4") (pin "12") (pinfunction "C_8_12") (pintype "bidirectional"))
      (node (ref "D4") (pin "13") (pinfunction "C_9_13") (pintype "bidirectional"))
      (node (ref "D4") (pin "14") (pinfunction "C_10_14") (pintype "bidirectional"))
      (node (ref "D4") (pin "15") (pinfunction "C_11_15") (pintype "bidirectional"))
      (node (ref "D4") (pin "5") (pinfunction "C_1_5") (pintype "bidirectional"))
      (node (ref "D4") (pin "6") (pinfunction "C_2_6") (pintype "bidirectional"))
      (node (ref "D4") (pin "7") (pinfunction "C_3_7") (pintype "bidirectional"))
      (node (ref "D4") (pin "8") (pinfunction "C_4_8") (pintype "bidirectional"))
      (node (ref "D4") (pin "9") (pinfunction "C_5_9") (pintype "bidirectional"))
      (node (ref "R2") (pin "1") (pinfunction "P$1_1") (pintype "passive"))
    )
    (net (code "29") (name "N$9") (class "Default")
      (node (ref "C1") (pin "2") (pinfunction "P$2_2") (pintype "passive"))
      (node (ref "D6") (pin "1") (pinfunction "A_1_1") (pintype "bidirectional"))
      (node (ref "D6") (pin "2") (pinfunction "A_2_2") (pintype "bidirectional"))
      (node (ref "D6") (pin "3") (pinfunction "A_3_3") (pintype "bidirectional"))
      (node (ref "D6") (pin "4") (pinfunction "A_4_4") (pintype "bidirectional"))
      (node (ref "R4") (pin "2") (pinfunction "P$2_2") (pintype "passive"))
    )
    (net (code "30") (name "Net-(C17-P$2)") (class "Default")
      (node (ref "C17") (pin "2") (pinfunction "P$2_2") (pintype "passive"))
      (node (ref "Q3") (pin "G") (pinfunction "Nｃｈ-G_G") (pintype "passive"))
      (node (ref "R32") (pin "2") (pinfunction "P$2_2") (pintype "passive"))
      (node (ref "R9") (pin "P$2") (pinfunction "P$2_P$2") (pintype "passive"))
    )
    (net (code "31") (name "Net-(C18-P$2)") (class "Default")
      (node (ref "C18") (pin "2") (pinfunction "P$2_2") (pintype "passive"))
      (node (ref "Q2") (pin "G") (pinfunction "Nｃｈ-G_G") (pintype "passive"))
      (node (ref "R12") (pin "P$2") (pinfunction "P$2_P$2") (pintype "passive"))
      (node (ref "R31") (pin "2") (pinfunction "P$2_2") (pintype "passive"))
    )
    (net (code "32") (name "Net-(C19-P$1)") (class "Default")
      (node (ref "C19") (pin "1") (pinfunction "P$1_1") (pintype "passive"))
      (node (ref "Q12") (pin "G") (pinfunction "Nｃｈ-G_G") (pintype "passive"))
      (node (ref "R13") (pin "P$1") (pinfunction "P$1_P$1") (pintype "passive"))
      (node (ref "R29") (pin "2") (pinfunction "P$2_2") (pintype "passive"))
    )
    (net (code "33") (name "Net-(C20-P$1)") (class "Default")
      (node (ref "C20") (pin "1") (pinfunction "P$1_1") (pintype "passive"))
      (node (ref "Q4") (pin "G") (pinfunction "Nｃｈ-G_G") (pintype "passive"))
      (node (ref "R17") (pin "P$1") (pinfunction "P$1_P$1") (pintype "passive"))
      (node (ref "R34") (pin "2") (pinfunction "P$2_2") (pintype "passive"))
    )
    (net (code "34") (name "Net-(D22-K)") (class "Default")
      (node (ref "D18") (pin "A") (pinfunction "A_A") (pintype "passive"))
      (node (ref "D22") (pin "1") (pinfunction "K_1") (pintype "bidirectional"))
      (node (ref "R27") (pin "2") (pinfunction "P$2_2") (pintype "passive"))
    )
    (net (code "35") (name "Net-(IC1-ANODE)") (class "Default")
      (node (ref "IC1") (pin "1") (pinfunction "ANODE_1") (pintype "bidirectional"))
      (node (ref "R7") (pin "2") (pinfunction "P$2_2") (pintype "passive"))
    )
    (net (code "36") (name "Net-(IC2-ANODE)") (class "Default")
      (node (ref "IC2") (pin "1") (pinfunction "ANODE_1") (pintype "bidirectional"))
      (node (ref "R5") (pin "2") (pinfunction "P$2_2") (pintype "passive"))
    )
    (net (code "37") (name "Net-(IC3-ANODE)") (class "Default")
      (node (ref "IC3") (pin "1") (pinfunction "ANODE_1") (pintype "bidirectional"))
      (node (ref "R6") (pin "2") (pinfunction "P$2_2") (pintype "passive"))
    )
    (net (code "38") (name "Net-(IC5-VOUT)") (class "Default")
      (node (ref "IC5") (pin "7") (pinfunction "VOUT_7") (pintype "bidirectional"))
      (node (ref "R30") (pin "1") (pinfunction "P$1_1") (pintype "passive"))
    )
    (net (code "39") (name "Net-(IC6-AN9_{slash}_CVD9_{slash}_RPA11_{slash}_FLT14_{slash}_RA11)") (class "Default")
      (node (ref "IC6") (pin "8") (pinfunction "AN9_/_CVD9_/_RPA11_/_FLT14_/_RA11_8") (pintype "bidirectional"))
      (node (ref "R16") (pin "2") (pinfunction "P$2_2") (pintype "passive"))
    )
    (net (code "40") (name "Net-(IC6-AN10_{slash}_CVD10_{slash}_RPA12_{slash}_FLT13_{slash}_RA12)") (class "Default")
      (node (ref "IC6") (pin "7") (pinfunction "AN10_/_CVD10_/_RPA12_/_FLT13_/_RA12_7") (pintype "bidirectional"))
      (node (ref "R15") (pin "2") (pinfunction "P$2_2") (pintype "passive"))
    )
    (net (code "41") (name "Net-(IC6-PGC3_{slash}_OA1OUT_{slash}_VREF+_{slash}_AN3_{slash}_C1IN4-_{slash}_C4IN2-_{slash}_RPB1_{slash}CTED1_{slash}_RB1)") (class "Default")
      (node (ref "IC6") (pin "12") (pinfunction "PGC3_/_OA1OUT_/_VREF+_/_AN3_/_C1IN4-_/_C4IN2-_/_RPB1_/CTED1_/_RB1_12") (pintype "bidirectional"))
      (node (ref "R23") (pin "2") (pinfunction "P$2_2") (pintype "passive"))
    )
    (net (code "42") (name "Net-(IC6-PGD3_{slash}_VREF-_{slash}_OA2IN-_{slash}_AN2_{slash}_C2IN1-_{slash}_RPB0_{slash}_CTED2_{slash}_RB0)") (class "Default")
      (node (ref "IC6") (pin "11") (pinfunction "PGD3_/_VREF-_/_OA2IN-_/_AN2_/_C2IN1-_/_RPB0_/_CTED2_/_RB0_11") (pintype "bidirectional"))
      (node (ref "R24") (pin "2") (pinfunction "P$2_2") (pintype "passive"))
    )
    (net (code "43") (name "Net-(IC8-CANH)") (class "Default")
      (node (ref "IC8") (pin "7") (pinfunction "CANH_7") (pintype "bidirectional"))
      (node (ref "J2") (pin "2") (pinfunction "2_2") (pintype "bidirectional"))
    )
    (net (code "44") (name "Net-(IC8-CANL)") (class "Default")
      (node (ref "IC8") (pin "6") (pinfunction "CANL_6") (pintype "bidirectional"))
      (node (ref "J2") (pin "3") (pinfunction "3_3") (pintype "bidirectional"))
    )
    (net (code "45") (name "Net-(IC13-ANODE)") (class "Default")
      (node (ref "IC13") (pin "1") (pinfunction "ANODE_1") (pintype "bidirectional"))
      (node (ref "R8") (pin "2") (pinfunction "P$2_2") (pintype "passive"))
    )
    (net (code "46") (name "Net-(R10-P$1)") (class "Default")
      (node (ref "R10") (pin "1") (pinfunction "P$1_1") (pintype "passive"))
      (node (ref "R11") (pin "1") (pinfunction "P$1_1") (pintype "passive"))
      (node (ref "S1") (pin "2") (pinfunction "NO_2") (pintype "bidirectional"))
    )
    (net (code "47") (name "Net-(R14-P$1)") (class "Default")
      (node (ref "D12") (pin "A") (pinfunction "A_A") (pintype "passive"))
      (node (ref "R14") (pin "1") (pinfunction "P$1_1") (pintype "passive"))
    )
    (net (code "48") (name "Net-(R15-P$1)") (class "Default")
      (node (ref "D9") (pin "A") (pinfunction "A_A") (pintype "passive"))
      (node (ref "R15") (pin "1") (pinfunction "P$1_1") (pintype "passive"))
    )
    (net (code "49") (name "Net-(R16-P$1)") (class "Default")
      (node (ref "D2") (pin "A") (pinfunction "A_A") (pintype "passive"))
      (node (ref "R16") (pin "1") (pinfunction "P$1_1") (pintype "passive"))
    )
    (net (code "50") (name "Net-(R22-P$1)") (class "Default")
      (node (ref "D10") (pin "A") (pinfunction "A_A") (pintype "passive"))
      (node (ref "R22") (pin "1") (pinfunction "P$1_1") (pintype "passive"))
    )
    (net (code "51") (name "Net-(R23-P$1)") (class "Default")
      (node (ref "D15") (pin "A") (pinfunction "A_A") (pintype "passive"))
      (node (ref "R23") (pin "1") (pinfunction "P$1_1") (pintype "passive"))
    )
    (net (code "52") (name "Net-(R24-P$1)") (class "Default")
      (node (ref "D11") (pin "A") (pinfunction "A_A") (pintype "passive"))
      (node (ref "R24") (pin "1") (pinfunction "P$1_1") (pintype "passive"))
    )
    (net (code "53") (name "Net-(R25-P$1)") (class "Default")
      (node (ref "J2") (pin "1") (pinfunction "1_1") (pintype "bidirectional"))
      (node (ref "R25") (pin "1") (pinfunction "P$1_1") (pintype "passive"))
    )
    (net (code "54") (name "Net-(R26-P$2)") (class "Default")
      (node (ref "Q1") (pin "B") (pinfunction "B_B") (pintype "passive"))
      (node (ref "R26") (pin "2") (pinfunction "P$2_2") (pintype "passive"))
    )
    (net (code "55") (name "Net-(R28-P$1)") (class "Default")
      (node (ref "D20") (pin "A") (pinfunction "A_A") (pintype "passive"))
      (node (ref "R28") (pin "1") (pinfunction "P$1_1") (pintype "passive"))
    )
    (net (code "56") (name "Net-(U1-POLARITY_PAD_(-))") (class "Default")
      (node (ref "Q1") (pin "C") (pinfunction "C_C") (pintype "passive"))
      (node (ref "U1") (pin "2") (pinfunction "POLARITY_PAD_(-)_2") (pintype "bidirectional"))
    )
    (net (code "57") (name "OSCI") (class "Default")
      (node (ref "C22") (pin "1") (pinfunction "P$1_1") (pintype "passive"))
      (node (ref "IC6") (pin "27") (pinfunction "OSCI_/_CLKI_/_AN49_/_CVD49_/_RPC12_/_RC12'_27") (pintype "bidirectional"))
      (node (ref "LGND") (pin "3") (pinfunction "CRYSTAL_2_3") (pintype "bidirectional"))
    )
    (net (code "58") (name "OSCO") (class "Default")
      (node (ref "C21") (pin "1") (pinfunction "P$1_1") (pintype "passive"))
      (node (ref "IC6") (pin "28") (pinfunction "OSCO_/_CLKO_/_RPC15_/_RC15_28") (pintype "bidirectional"))
      (node (ref "LGND") (pin "1") (pinfunction "CRYSTAL_1_1") (pintype "bidirectional"))
    )
    (net (code "59") (name "PGEC") (class "Default")
      (node (ref "IC6") (pin "13") (pinfunction "PGC1_/_OA1IN+_/_AN4_/_C1IN1+_/_C1IN3-_/_C2IN3-_/_RPB2_/_RB2_13") (pintype "bidirectional"))
      (node (ref "JP1") (pin "5") (pinfunction "5_5") (pintype "passive"))
    )
    (net (code "60") (name "PGED") (class "Default")
      (node (ref "IC6") (pin "14") (pinfunction "PGD1_/_OA1IN-_/_AN5_/_CTCMP_/_C1IN1-_/_RTCC_/_RPB3_/_RB3_14") (pintype "bidirectional"))
      (node (ref "JP1") (pin "4") (pinfunction "4_4") (pintype "passive"))
    )
    (net (code "61") (name "PGND") (class "Default")
      (node (ref "C13") (pin "2") (pinfunction "-_2") (pintype "passive"))
      (node (ref "C16") (pin "2") (pinfunction "P$2_2") (pintype "passive"))
      (node (ref "C23") (pin "2") (pinfunction "P$2_2") (pintype "passive"))
      (node (ref "C25") (pin "2") (pinfunction "P$2_2") (pintype "passive"))
      (node (ref "C28") (pin "1") (pinfunction "P$1_1") (pintype "passive"))
      (node (ref "C3") (pin "2") (pinfunction "P$2_2") (pintype "passive"))
      (node (ref "C4") (pin "2") (pinfunction "P$2_2") (pintype "passive"))
      (node (ref "C5") (pin "1") (pinfunction "P$1_1") (pintype "passive"))
      (node (ref "CON2") (pin "+") (pinfunction "+_+") (pintype "power_in"))
      (node (ref "D13") (pin "1") (pinfunction "A_1_1") (pintype "bidirectional"))
      (node (ref "D13") (pin "2") (pinfunction "A_2_2") (pintype "bidirectional"))
      (node (ref "D13") (pin "3") (pinfunction "A_3_3") (pintype "bidirectional"))
      (node (ref "D13") (pin "4") (pinfunction "A_4_4") (pintype "bidirectional"))
      (node (ref "D14") (pin "1") (pinfunction "A_1_1") (pintype "bidirectional"))
      (node (ref "D14") (pin "2") (pinfunction "A_2_2") (pintype "bidirectional"))
      (node (ref "D14") (pin "3") (pinfunction "A_3_3") (pintype "bidirectional"))
      (node (ref "D14") (pin "4") (pinfunction "A_4_4") (pintype "bidirectional"))
      (node (ref "D18") (pin "C") (pinfunction "C_C") (pintype "passive"))
      (node (ref "IC1") (pin "4") (pinfunction "GND_4") (pintype "bidirectional"))
      (node (ref "IC11") (pin "2") (pinfunction "GND_2") (pintype "input"))
      (node (ref "IC12") (pin "2") (pinfunction "GND_2") (pintype "input"))
      (node (ref "IC3") (pin "4") (pinfunction "GND_4") (pintype "bidirectional"))
      (node (ref "PS1") (pin "1") (pinfunction "-VIN_1") (pintype "bidirectional"))
      (node (ref "PS2") (pin "1") (pinfunction "-VIN_1") (pintype "bidirectional"))
      (node (ref "Q12") (pin "S1") (pinfunction "NｃｈS_S1") (pintype "passive"))
      (node (ref "Q12") (pin "S2") (pinfunction "NｃｈS_S2") (pintype "passive"))
      (node (ref "Q12") (pin "S3") (pinfunction "NｃｈS_S3") (pintype "passive"))
      (node (ref "Q12") (pin "S4") (pinfunction "NｃｈS_S4") (pintype "passive"))
      (node (ref "Q12") (pin "S5") (pinfunction "NｃｈS_S5") (pintype "passive"))
      (node (ref "Q2") (pin "S1") (pinfunction "NｃｈS_S1") (pintype "passive"))
      (node (ref "Q2") (pin "S2") (pinfunction "NｃｈS_S2") (pintype "passive"))
      (node (ref "Q2") (pin "S3") (pinfunction "NｃｈS_S3") (pintype "passive"))
      (node (ref "Q2") (pin "S4") (pinfunction "NｃｈS_S4") (pintype "passive"))
      (node (ref "Q2") (pin "S5") (pinfunction "NｃｈS_S5") (pintype "passive"))
      (node (ref "R27") (pin "1") (pinfunction "P$1_1") (pintype "passive"))
      (node (ref "R29") (pin "1") (pinfunction "P$1_1") (pintype "passive"))
      (node (ref "R31") (pin "1") (pinfunction "P$1_1") (pintype "passive"))
      (node (ref "SCREW2") (pin "P$1") (pinfunction "P$1_P$1") (pintype "bidirectional"))
      (node (ref "SCREW2") (pin "P$2") (pinfunction "P$1_P$2") (pintype "bidirectional"))
    )
    (net (code "62") (name "PWM1_HIGH") (class "Default")
      (node (ref "IC6") (pin "40") (pinfunction "RPC8_/_PWM5H_/_RC8_40") (pintype "bidirectional"))
      (node (ref "R8") (pin "1") (pinfunction "P$1_1") (pintype "passive"))
    )
    (net (code "63") (name "PWM1_LOW") (class "Default")
      (node (ref "IC6") (pin "41") (pinfunction "RPC9_/_PWM5L_/_RC9_41") (pintype "bidirectional"))
      (node (ref "R7") (pin "1") (pinfunction "P$1_1") (pintype "passive"))
    )
    (net (code "64") (name "PWM2_HIGH") (class "Default")
      (node (ref "IC6") (pin "38") (pinfunction "RPC6_/_PWM6H_/_RC6_38") (pintype "bidirectional"))
      (node (ref "R5") (pin "1") (pinfunction "P$1_1") (pintype "passive"))
    )
    (net (code "65") (name "PWM2_LOW") (class "Default")
      (node (ref "IC6") (pin "39") (pinfunction "RPC7_/_PWM6L_/_RC7_39") (pintype "bidirectional"))
      (node (ref "R6") (pin "1") (pinfunction "P$1_1") (pintype "passive"))
    )
    (net (code "66") (name "ROTA1") (class "Default")
      (node (ref "IC6") (pin "31") (pinfunction "PGD2_/_RPB5_/_SDA1_/_RB5_31") (pintype "bidirectional"))
      (node (ref "R21") (pin "1") (pinfunction "P$1_1") (pintype "passive"))
      (node (ref "S2") (pin "1") (pinfunction "1_1") (pintype "bidirectional"))
    )
    (net (code "67") (name "ROTA2") (class "Default")
      (node (ref "IC6") (pin "32") (pinfunction "PGC2_/_RPB6_/_SCL1_/_RB6_32") (pintype "bidirectional"))
      (node (ref "R20") (pin "1") (pinfunction "P$1_1") (pintype "passive"))
      (node (ref "S2") (pin "2") (pinfunction "2_2") (pintype "bidirectional"))
    )
    (net (code "68") (name "ROTA4") (class "Default")
      (node (ref "IC6") (pin "34") (pinfunction "OA5OUT_/_AN25_/_CVD25_/_C5IN4-_/_RPB7_/_SCK1_/_INT0_/_RB7_34") (pintype "bidirectional"))
      (node (ref "R19") (pin "1") (pinfunction "P$1_1") (pintype "passive"))
      (node (ref "S2") (pin "3") (pinfunction "3_3") (pintype "bidirectional"))
    )
    (net (code "69") (name "ROTA8") (class "Default")
      (node (ref "IC6") (pin "36") (pinfunction "SOSCO_/_RPB8(5)_/T1CK(5)_/_RB8(5)_36") (pintype "bidirectional"))
      (node (ref "R18") (pin "1") (pinfunction "P$1_1") (pintype "passive"))
      (node (ref "S2") (pin "4") (pinfunction "4_4") (pintype "bidirectional"))
    )
    (net (code "70") (name "VDD") (class "Default")
      (node (ref "C1") (pin "1") (pinfunction "P$1_1") (pintype "passive"))
      (node (ref "C2") (pin "1") (pinfunction "P$1_1") (pintype "passive"))
      (node (ref "C25") (pin "1") (pinfunction "P$1_1") (pintype "passive"))
      (node (ref "D16") (pin "C") (pinfunction "C_C") (pintype "passive"))
      (node (ref "D17") (pin "C") (pinfunction "C_C") (pintype "passive"))
      (node (ref "D7") (pin "10") (pinfunction "C_6_10") (pintype "bidirectional"))
      (node (ref "D7") (pin "11") (pinfunction "C_7_11") (pintype "bidirectional"))
      (node (ref "D7") (pin "12") (pinfunction "C_8_12") (pintype "bidirectional"))
      (node (ref "D7") (pin "13") (pinfunction "C_9_13") (pintype "bidirectional"))
      (node (ref "D7") (pin "14") (pinfunction "C_10_14") (pintype "bidirectional"))
      (node (ref "D7") (pin "15") (pinfunction "C_11_15") (pintype "bidirectional"))
      (node (ref "D7") (pin "5") (pinfunction "C_1_5") (pintype "bidirectional"))
      (node (ref "D7") (pin "6") (pinfunction "C_2_6") (pintype "bidirectional"))
      (node (ref "D7") (pin "7") (pinfunction "C_3_7") (pintype "bidirectional"))
      (node (ref "D7") (pin "8") (pinfunction "C_4_8") (pintype "bidirectional"))
      (node (ref "D7") (pin "9") (pinfunction "C_5_9") (pintype "bidirectional"))
      (node (ref "D8") (pin "10") (pinfunction "C_6_10") (pintype "bidirectional"))
      (node (ref "D8") (pin "11") (pinfunction "C_7_11") (pintype "bidirectional"))
      (node (ref "D8") (pin "12") (pinfunction "C_8_12") (pintype "bidirectional"))
      (node (ref "D8") (pin "13") (pinfunction "C_9_13") (pintype "bidirectional"))
      (node (ref "D8") (pin "14") (pinfunction "C_10_14") (pintype "bidirectional"))
      (node (ref "D8") (pin "15") (pinfunction "C_11_15") (pintype "bidirectional"))
      (node (ref "D8") (pin "5") (pinfunction "C_1_5") (pintype "bidirectional"))
      (node (ref "D8") (pin "6") (pinfunction "C_2_6") (pintype "bidirectional"))
      (node (ref "D8") (pin "7") (pinfunction "C_3_7") (pintype "bidirectional"))
      (node (ref "D8") (pin "8") (pinfunction "C_4_8") (pintype "bidirectional"))
      (node (ref "D8") (pin "9") (pinfunction "C_5_9") (pintype "bidirectional"))
      (node (ref "IC11") (pin "1") (pinfunction "IN_1") (pintype "input"))
      (node (ref "IC12") (pin "1") (pinfunction "IN_1") (pintype "input"))
      (node (ref "IC5") (pin "3") (pinfunction "IN-_1_3") (pintype "bidirectional"))
      (node (ref "IC5") (pin "4") (pinfunction "IN-_2_4") (pintype "bidirectional"))
      (node (ref "Q3") (pin "D") (pinfunction "NｃｈD_D") (pintype "passive"))
      (node (ref "Q4") (pin "D") (pinfunction "NｃｈD_D") (pintype "passive"))
    )
    (net (code "71") (name "X") (class "Default")
      (node (ref "IC6") (pin "45") (pinfunction "RPB11_/_PWM3L_/_RB11_45") (pintype "bidirectional"))
      (node (ref "J1") (pin "4") (pinfunction "4_4") (pintype "bidirectional"))
    )
    (net (code "72") (name "unconnected-(IC5-NC-Pad6)") (class "Default")
      (node (ref "IC5") (pin "6") (pinfunction "NC_6") (pintype "no_connect"))
    )
    (net (code "73") (name "unconnected-(IC6-AN11_{slash}_CVD11_{slash}_C1IN2-_{slash}_FLT4_{slash}_RC11-Pad20)") (class "Default")
      (node (ref "IC6") (pin "20") (pinfunction "AN11_/_CVD11_/_C1IN2-_/_FLT4_/_RC11_20") (pintype "bidirectional"))
    )
    (net (code "74") (name "unconnected-(IC6-DAC1_{slash}_AN48_{slash}_CVD48_{slash}_RPC10_{slash}_RC10-Pad33)") (class "Default")
      (node (ref "IC6") (pin "33") (pinfunction "DAC1_/_AN48_/_CVD48_/_RPC10_/_RC10_33") (pintype "bidirectional"))
    )
    (net (code "75") (name "unconnected-(IC6-FLT15_{slash}_RPB4_{slash}_SCL2_{slash}_RB4-Pad24)") (class "Default")
      (node (ref "IC6") (pin "24") (pinfunction "FLT15_/_RPB4_/_SCL2_/_RB4_24") (pintype "bidirectional"))
    )
    (net (code "76") (name "unconnected-(IC6-OA3IN+_{slash}_AN8_{slash}_CVD8_{slash}_C3IN1+_{slash}_C3IN3-_{slash}_RPC2_{slash}_FLT3_{slash}_RC2-Pad19)") (class "Default")
      (node (ref "IC6") (pin "19") (pinfunction "OA3IN+_/_AN8_/_CVD8_/_C3IN1+_/_C3IN3-_/_RPC2_/_FLT3_/_RC2_19") (pintype "bidirectional"))
    )
    (net (code "77") (name "unconnected-(IC6-OA3IN-_{slash}_AN7_{slash}_CVD7_{slash}_C3IN1-_{slash}_C4IN1-_{slash}_RPC1_{slash}_RC1-Pad18)") (class "Default")
      (node (ref "IC6") (pin "18") (pinfunction "OA3IN-_/_AN7_/_CVD7_/_C3IN1-_/_C4IN1-_/_RPC1_/_RC1_18") (pintype "bidirectional"))
    )
    (net (code "78") (name "unconnected-(IC6-OA3OUT_{slash}_AN6_{slash}_CVD6_{slash}_C3IN4-_{slash}_C4IN1+_{slash}_C4IN4-_{slash}_RPC0_{slash}_RC0-Pad17)") (class "Default")
      (node (ref "IC6") (pin "17") (pinfunction "OA3OUT_/_AN6_/_CVD6_/_C3IN4-_/_C4IN1+_/_C4IN4-_/_RPC0_/_RC0_17") (pintype "bidirectional"))
    )
    (net (code "79") (name "unconnected-(IC6-RD8-Pad30)") (class "Default")
      (node (ref "IC6") (pin "30") (pinfunction "RD8_30") (pintype "bidirectional"))
    )
    (net (code "80") (name "unconnected-(IC6-RPB12_{slash}_PWM2H_{slash}_RB12-Pad46)") (class "Default")
      (node (ref "IC6") (pin "46") (pinfunction "RPB12_/_PWM2H_/_RB12_46") (pintype "bidirectional"))
    )
    (net (code "81") (name "unconnected-(IC6-SOSCI_{slash}_RPC13(5)_{slash}_RC13(5)-Pad35)") (class "Default")
      (node (ref "IC6") (pin "35") (pinfunction "SOSCI_/_RPC13(5)_/_RC13(5)_35") (pintype "bidirectional"))
    )
    (net (code "82") (name "unconnected-(IC6-TMS_{slash}_OA5IN-_{slash}_AN27_{slash}_CVD27_{slash}_LVDIN_{slash}_C5IN1-_{slash}_RPB9_{slash}_RB9-Pad37)") (class "Default")
      (node (ref "IC6") (pin "37") (pinfunction "TMS_/_OA5IN-_/_AN27_/_CVD27_/_LVDIN_/_C5IN1-_/_RPB9_/_RB9_37") (pintype "bidirectional"))
    )
    (net (code "83") (name "unconnected-(PS1-NO_CONNECTION-Pad8)") (class "Default")
      (node (ref "PS1") (pin "8") (pinfunction "NO_CONNECTION_8") (pintype "bidirectional"))
    )
    (net (code "84") (name "unconnected-(PS2-NO_CONNECTION-Pad8)") (class "Default")
      (node (ref "PS2") (pin "8") (pinfunction "NO_CONNECTION_8") (pintype "bidirectional"))
    )
  )
)
